# smartwatch_class_2_bottom.net
KiCad netlist of a schematic drawn in EAGLE
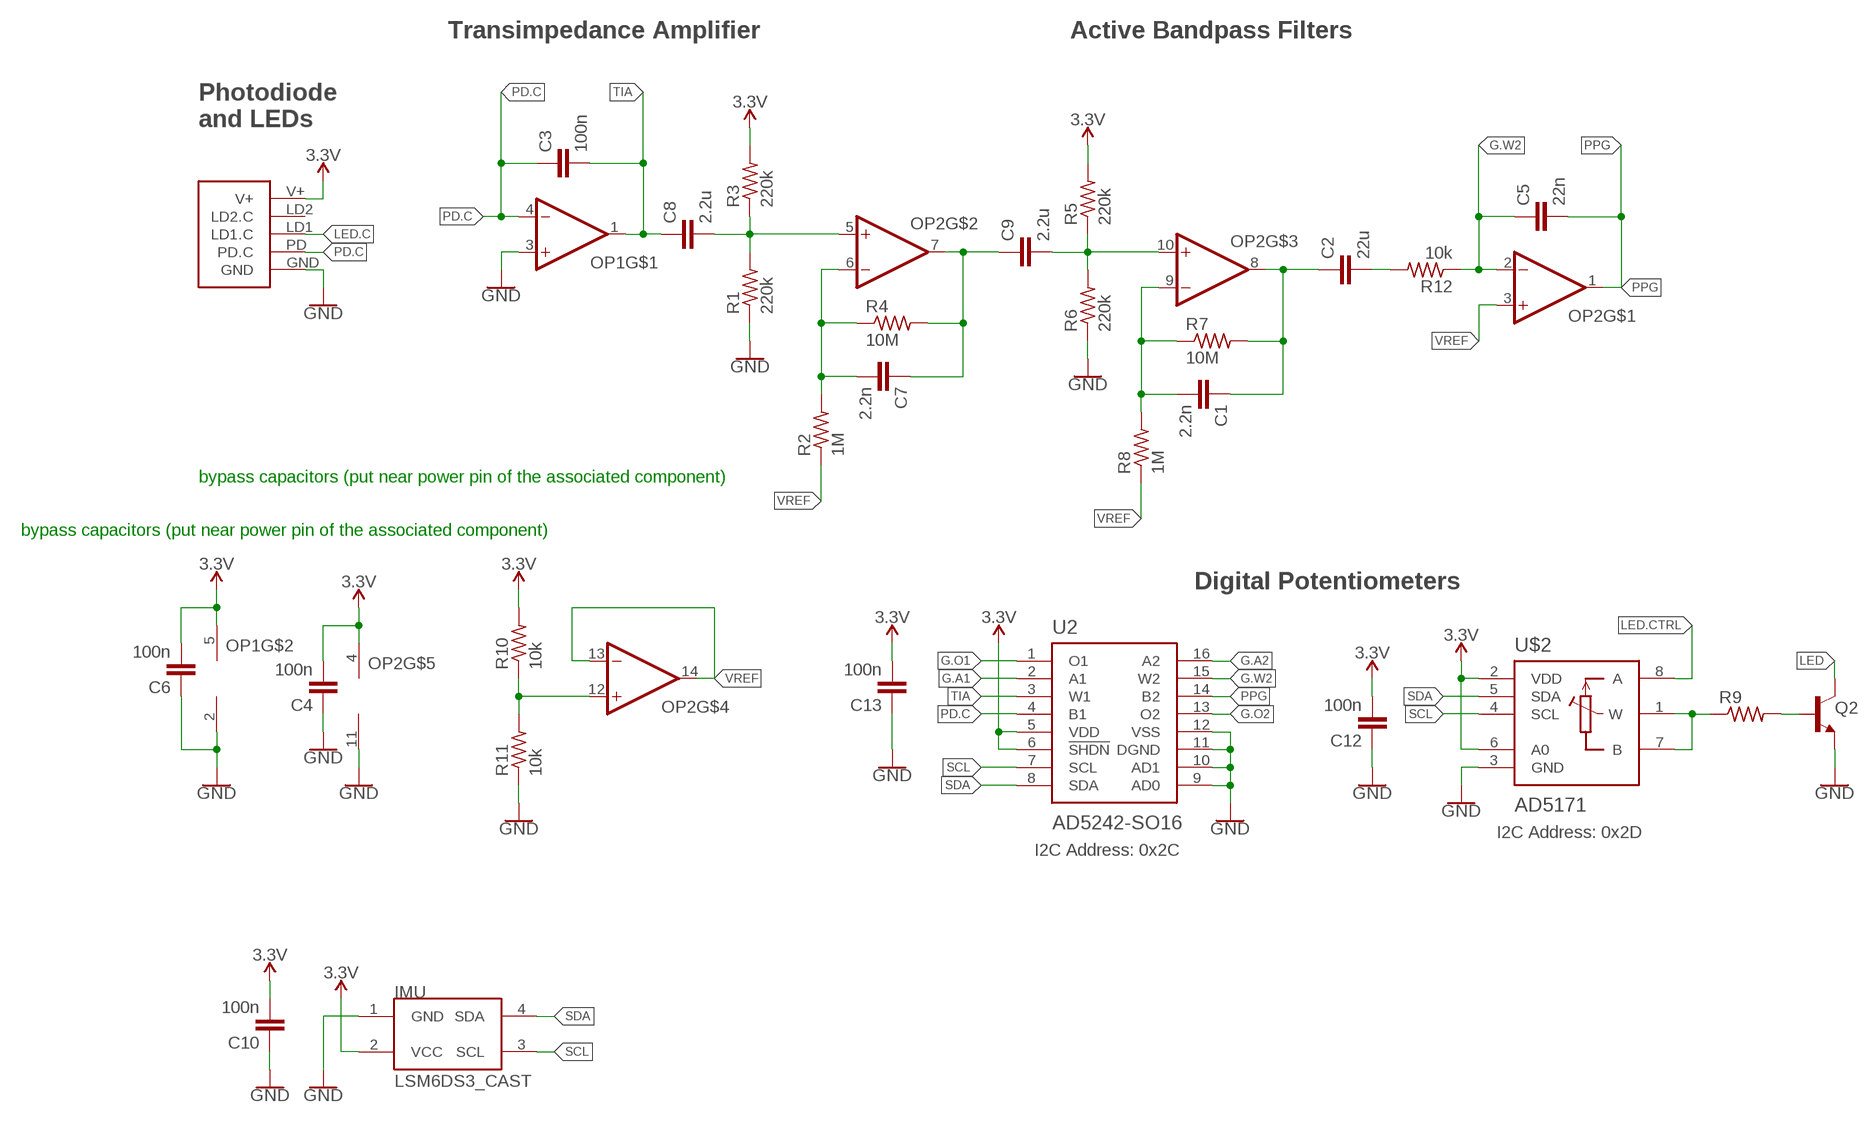
[diagram p0: schematic, sheet 1]

(export (version "E")
  (design (tool "Eeschema 10.0.6"))
  (components
    (comp (ref "C1")
      (value "2.2n")
      (footprint "eagle-import:C0603")
      (libsource (lib "eagle-import") (part "CAPACITOR0603"))
    )
    (comp (ref "C2")
      (value "22u")
      (footprint "eagle-import:C0603")
      (libsource (lib "eagle-import") (part "CAPACITOR0603"))
    )
    (comp (ref "C3")
      (value "100n")
      (footprint "eagle-import:C0603")
      (libsource (lib "eagle-import") (part "CAPACITOR0603"))
    )
    (comp (ref "C4")
      (value "100n")
      (footprint "eagle-import:C0603")
      (libsource (lib "eagle-import") (part "CAPACITOR0603"))
    )
    (comp (ref "C5")
      (value "22n")
      (footprint "eagle-import:C0603")
      (libsource (lib "eagle-import") (part "CAPACITOR0603"))
    )
    (comp (ref "C6")
      (value "100n")
      (footprint "eagle-import:C0603")
      (libsource (lib "eagle-import") (part "CAPACITOR0603"))
    )
    (comp (ref "C7")
      (value "2.2n")
      (footprint "eagle-import:C0603")
      (libsource (lib "eagle-import") (part "CAPACITOR0603"))
    )
    (comp (ref "C8")
      (value "2.2u")
      (footprint "eagle-import:C0603")
      (libsource (lib "eagle-import") (part "CAPACITOR0603"))
    )
    (comp (ref "C9")
      (value "2.2u")
      (footprint "eagle-import:C0603")
      (libsource (lib "eagle-import") (part "CAPACITOR0603"))
    )
    (comp (ref "C10")
      (value "100n")
      (footprint "eagle-import:C0603")
      (libsource (lib "eagle-import") (part "CAPACITOR0603"))
    )
    (comp (ref "C12")
      (value "100n")
      (footprint "eagle-import:C0603")
      (libsource (lib "eagle-import") (part "CAPACITOR0603"))
    )
    (comp (ref "C13")
      (value "100n")
      (footprint "eagle-import:C0603")
      (libsource (lib "eagle-import") (part "CAPACITOR0603"))
    )
    (comp (ref "IMU")
      (value "LSM6DS3_CAST")
      (footprint "eagle-import:LSM6DS3_CAST")
      (libsource (lib "eagle-import") (part "LSM6DS3_CAST"))
    )
    (comp (ref "OP1")
      (value "OP-SINGLEOT")
      (footprint "eagle-import:SOT23-5")
      (libsource (lib "eagle-import") (part "OP-SINGLEOT"))
    )
    (comp (ref "OP2")
      (value "OP-QUAD-SO14")
      (footprint "eagle-import:SO14")
      (libsource (lib "eagle-import") (part "OP-QUAD-SO14"))
    )
    (comp (ref "Q2")
      (value "NPN-GENERIC")
      (footprint "eagle-import:SOT23-3")
      (libsource (lib "eagle-import") (part "NPN-GENERIC"))
    )
    (comp (ref "R1")
      (value "220k")
      (footprint "eagle-import:R0603")
      (libsource (lib "eagle-import") (part "RESISTOR0603"))
    )
    (comp (ref "R2")
      (value "1M")
      (footprint "eagle-import:R0603")
      (libsource (lib "eagle-import") (part "RESISTOR0603"))
    )
    (comp (ref "R3")
      (value "220k")
      (footprint "eagle-import:R0603")
      (libsource (lib "eagle-import") (part "RESISTOR0603"))
    )
    (comp (ref "R4")
      (value "10M")
      (footprint "eagle-import:R0603")
      (libsource (lib "eagle-import") (part "RESISTOR0603"))
    )
    (comp (ref "R5")
      (value "220k")
      (footprint "eagle-import:R0603")
      (libsource (lib "eagle-import") (part "RESISTOR0603"))
    )
    (comp (ref "R6")
      (value "220k")
      (footprint "eagle-import:R0603")
      (libsource (lib "eagle-import") (part "RESISTOR0603"))
    )
    (comp (ref "R7")
      (value "10M")
      (footprint "eagle-import:R0603")
      (libsource (lib "eagle-import") (part "RESISTOR0603"))
    )
    (comp (ref "R8")
      (value "1M")
      (footprint "eagle-import:R0603")
      (libsource (lib "eagle-import") (part "RESISTOR0603"))
    )
    (comp (ref "R9")
      (value "RESISTOR0603")
      (footprint "eagle-import:R0603")
      (libsource (lib "eagle-import") (part "RESISTOR0603"))
    )
    (comp (ref "R10")
      (value "10k")
      (footprint "eagle-import:R0402")
      (libsource (lib "eagle-import") (part "RESISTOR0402"))
    )
    (comp (ref "R11")
      (value "10k")
      (footprint "eagle-import:R0402")
      (libsource (lib "eagle-import") (part "RESISTOR0402"))
    )
    (comp (ref "R12")
      (value "10k")
      (footprint "eagle-import:R0603")
      (libsource (lib "eagle-import") (part "RESISTOR0603"))
    )
    (comp (ref "U$1")
      (value "PPG.MODULE.2")
      (footprint "eagle-import:PPG.MODULE.2")
      (libsource (lib "eagle-import") (part "PPG.MODULE.2"))
    )
    (comp (ref "U$2")
      (value "AD5171")
      (footprint "eagle-import:SOT-23-8")
      (libsource (lib "eagle-import") (part "AD5171"))
    )
    (comp (ref "U2")
      (value "AD5242-SO16")
      (footprint "eagle-import:SO16")
      (libsource (lib "eagle-import") (part "AD5242-SO16"))
    )
  )
  (nets
    (net (code "1") (name "3.3V") (class "Default")
      (node (ref "C10") (pin "2") (pinfunction "2_2") (pintype "passive"))
      (node (ref "C12") (pin "2") (pinfunction "2_2") (pintype "passive"))
      (node (ref "C13") (pin "2") (pinfunction "2_2") (pintype "passive"))
      (node (ref "C4") (pin "2") (pinfunction "2_2") (pintype "passive"))
      (node (ref "C6") (pin "2") (pinfunction "2_2") (pintype "passive"))
      (node (ref "IMU") (pin "2") (pinfunction "VCC_2") (pintype "bidirectional"))
      (node (ref "OP1") (pin "5") (pinfunction "V+_5") (pintype "power_in"))
      (node (ref "OP2") (pin "4") (pinfunction "V+_4") (pintype "power_in"))
      (node (ref "R10") (pin "2") (pinfunction "2_2") (pintype "passive"))
      (node (ref "R3") (pin "2") (pinfunction "2_2") (pintype "passive"))
      (node (ref "R5") (pin "2") (pinfunction "2_2") (pintype "passive"))
      (node (ref "U$1") (pin "V+") (pinfunction "V+_V+") (pintype "bidirectional"))
      (node (ref "U$2") (pin "2") (pinfunction "VDD_2") (pintype "bidirectional"))
      (node (ref "U$2") (pin "6") (pinfunction "A0_6") (pintype "bidirectional"))
      (node (ref "U2") (pin "5") (pinfunction "VDD_5") (pintype "bidirectional"))
      (node (ref "U2") (pin "6") (pinfunction "~{SHDN}_6") (pintype "bidirectional"))
    )
    (net (code "2") (name "G.A1") (class "Default")
      (node (ref "U2") (pin "2") (pinfunction "A1_2") (pintype "bidirectional"))
    )
    (net (code "3") (name "G.A2") (class "Default")
      (node (ref "U2") (pin "16") (pinfunction "A2_16") (pintype "bidirectional"))
    )
    (net (code "4") (name "G.O1") (class "Default")
      (node (ref "U2") (pin "1") (pinfunction "O1_1") (pintype "bidirectional"))
    )
    (net (code "5") (name "G.O2") (class "Default")
      (node (ref "U2") (pin "13") (pinfunction "O2_13") (pintype "bidirectional"))
    )
    (net (code "6") (name "G.W2") (class "Default")
      (node (ref "C5") (pin "1") (pinfunction "1_1") (pintype "passive"))
      (node (ref "OP2") (pin "2") (pinfunction "-IN_2") (pintype "input"))
      (node (ref "R12") (pin "1") (pinfunction "1_1") (pintype "passive"))
      (node (ref "U2") (pin "15") (pinfunction "W2_15") (pintype "bidirectional"))
    )
    (net (code "7") (name "GND") (class "Default")
      (node (ref "C10") (pin "1") (pinfunction "1_1") (pintype "passive"))
      (node (ref "C12") (pin "1") (pinfunction "1_1") (pintype "passive"))
      (node (ref "C13") (pin "1") (pinfunction "1_1") (pintype "passive"))
      (node (ref "C4") (pin "1") (pinfunction "1_1") (pintype "passive"))
      (node (ref "C6") (pin "1") (pinfunction "1_1") (pintype "passive"))
      (node (ref "IMU") (pin "1") (pinfunction "GND_1") (pintype "bidirectional"))
      (node (ref "OP1") (pin "2") (pinfunction "V-_2") (pintype "power_in"))
      (node (ref "OP1") (pin "3") (pinfunction "+IN_3") (pintype "input"))
      (node (ref "OP2") (pin "11") (pinfunction "V-_11") (pintype "power_in"))
      (node (ref "Q2") (pin "2") (pinfunction "E_2") (pintype "passive"))
      (node (ref "R1") (pin "1") (pinfunction "1_1") (pintype "passive"))
      (node (ref "R11") (pin "1") (pinfunction "1_1") (pintype "passive"))
      (node (ref "R6") (pin "1") (pinfunction "1_1") (pintype "passive"))
      (node (ref "U$1") (pin "GND") (pinfunction "GND_GND") (pintype "bidirectional"))
      (node (ref "U$2") (pin "3") (pinfunction "GND_3") (pintype "bidirectional"))
      (node (ref "U2") (pin "10") (pinfunction "AD1_10") (pintype "bidirectional"))
      (node (ref "U2") (pin "11") (pinfunction "DGND_11") (pintype "bidirectional"))
      (node (ref "U2") (pin "12") (pinfunction "VSS_12") (pintype "bidirectional"))
      (node (ref "U2") (pin "9") (pinfunction "AD0_9") (pintype "bidirectional"))
    )
    (net (code "8") (name "LED") (class "Default")
      (node (ref "Q2") (pin "3") (pinfunction "C_3") (pintype "passive"))
    )
    (net (code "9") (name "LED.C") (class "Default")
      (node (ref "U$1") (pin "LD1") (pinfunction "LD1.C_LD1") (pintype "bidirectional"))
    )
    (net (code "10") (name "LED.CTRL") (class "Default")
      (node (ref "U$2") (pin "8") (pinfunction "A_8") (pintype "bidirectional"))
    )
    (net (code "11") (name "Net-(C2-Pad2)") (class "Default")
      (node (ref "C2") (pin "2") (pinfunction "2_2") (pintype "passive"))
      (node (ref "R12") (pin "2") (pinfunction "2_2") (pintype "passive"))
    )
    (net (code "12") (name "Net-(OP2B-+IN)") (class "Default")
      (node (ref "C8") (pin "2") (pinfunction "2_2") (pintype "passive"))
      (node (ref "OP2") (pin "5") (pinfunction "+IN_5") (pintype "input"))
      (node (ref "R1") (pin "2") (pinfunction "2_2") (pintype "passive"))
      (node (ref "R3") (pin "1") (pinfunction "1_1") (pintype "passive"))
    )
    (net (code "13") (name "Net-(OP2B--IN)") (class "Default")
      (node (ref "C7") (pin "2") (pinfunction "2_2") (pintype "passive"))
      (node (ref "OP2") (pin "6") (pinfunction "-IN_6") (pintype "input"))
      (node (ref "R2") (pin "2") (pinfunction "2_2") (pintype "passive"))
      (node (ref "R4") (pin "1") (pinfunction "1_1") (pintype "passive"))
    )
    (net (code "14") (name "Net-(OP2B-OUT)") (class "Default")
      (node (ref "C7") (pin "1") (pinfunction "1_1") (pintype "passive"))
      (node (ref "C9") (pin "1") (pinfunction "1_1") (pintype "passive"))
      (node (ref "OP2") (pin "7") (pinfunction "OUT_7") (pintype "output"))
      (node (ref "R4") (pin "2") (pinfunction "2_2") (pintype "passive"))
    )
    (net (code "15") (name "Net-(OP2C-+IN)") (class "Default")
      (node (ref "C9") (pin "2") (pinfunction "2_2") (pintype "passive"))
      (node (ref "OP2") (pin "10") (pinfunction "+IN_10") (pintype "input"))
      (node (ref "R5") (pin "1") (pinfunction "1_1") (pintype "passive"))
      (node (ref "R6") (pin "2") (pinfunction "2_2") (pintype "passive"))
    )
    (net (code "16") (name "Net-(OP2C--IN)") (class "Default")
      (node (ref "C1") (pin "2") (pinfunction "2_2") (pintype "passive"))
      (node (ref "OP2") (pin "9") (pinfunction "-IN_9") (pintype "input"))
      (node (ref "R7") (pin "1") (pinfunction "1_1") (pintype "passive"))
      (node (ref "R8") (pin "2") (pinfunction "2_2") (pintype "passive"))
    )
    (net (code "17") (name "Net-(OP2C-OUT)") (class "Default")
      (node (ref "C1") (pin "1") (pinfunction "1_1") (pintype "passive"))
      (node (ref "C2") (pin "1") (pinfunction "1_1") (pintype "passive"))
      (node (ref "OP2") (pin "8") (pinfunction "OUT_8") (pintype "output"))
      (node (ref "R7") (pin "2") (pinfunction "2_2") (pintype "passive"))
    )
    (net (code "18") (name "Net-(OP2D-+IN)") (class "Default")
      (node (ref "OP2") (pin "12") (pinfunction "+IN_12") (pintype "input"))
      (node (ref "R10") (pin "1") (pinfunction "1_1") (pintype "passive"))
      (node (ref "R11") (pin "2") (pinfunction "2_2") (pintype "passive"))
    )
    (net (code "19") (name "Net-(Q2-B)") (class "Default")
      (node (ref "Q2") (pin "1") (pinfunction "B_1") (pintype "passive"))
      (node (ref "R9") (pin "2") (pinfunction "2_2") (pintype "passive"))
    )
    (net (code "20") (name "Net-(U$2-B)") (class "Default")
      (node (ref "R9") (pin "1") (pinfunction "1_1") (pintype "passive"))
      (node (ref "U$2") (pin "1") (pinfunction "W_1") (pintype "bidirectional"))
      (node (ref "U$2") (pin "7") (pinfunction "B_7") (pintype "bidirectional"))
    )
    (net (code "21") (name "PD.C") (class "Default")
      (node (ref "C3") (pin "1") (pinfunction "1_1") (pintype "passive"))
      (node (ref "OP1") (pin "4") (pinfunction "-IN_4") (pintype "input"))
      (node (ref "U$1") (pin "PD") (pinfunction "PD.C_PD") (pintype "bidirectional"))
      (node (ref "U2") (pin "4") (pinfunction "B1_4") (pintype "bidirectional"))
    )
    (net (code "22") (name "PPG") (class "Default")
      (node (ref "C5") (pin "2") (pinfunction "2_2") (pintype "passive"))
      (node (ref "OP2") (pin "1") (pinfunction "OUT_1") (pintype "output"))
      (node (ref "U2") (pin "14") (pinfunction "B2_14") (pintype "bidirectional"))
    )
    (net (code "23") (name "SCL") (class "Default")
      (node (ref "IMU") (pin "3") (pinfunction "SCL_3") (pintype "bidirectional"))
      (node (ref "U$2") (pin "4") (pinfunction "SCL_4") (pintype "bidirectional"))
      (node (ref "U2") (pin "7") (pinfunction "SCL_7") (pintype "bidirectional"))
    )
    (net (code "24") (name "SDA") (class "Default")
      (node (ref "IMU") (pin "4") (pinfunction "SDA_4") (pintype "bidirectional"))
      (node (ref "U$2") (pin "5") (pinfunction "SDA_5") (pintype "bidirectional"))
      (node (ref "U2") (pin "8") (pinfunction "SDA_8") (pintype "bidirectional"))
    )
    (net (code "25") (name "TIA") (class "Default")
      (node (ref "C3") (pin "2") (pinfunction "2_2") (pintype "passive"))
      (node (ref "C8") (pin "1") (pinfunction "1_1") (pintype "passive"))
      (node (ref "OP1") (pin "1") (pinfunction "OUT_1") (pintype "output"))
      (node (ref "U2") (pin "3") (pinfunction "W1_3") (pintype "bidirectional"))
    )
    (net (code "26") (name "VREF") (class "Default")
      (node (ref "OP2") (pin "13") (pinfunction "-IN_13") (pintype "input"))
      (node (ref "OP2") (pin "14") (pinfunction "OUT_14") (pintype "output"))
      (node (ref "OP2") (pin "3") (pinfunction "+IN_3") (pintype "input"))
      (node (ref "R2") (pin "1") (pinfunction "1_1") (pintype "passive"))
      (node (ref "R8") (pin "1") (pinfunction "1_1") (pintype "passive"))
    )
    (net (code "27") (name "unconnected-(U$1-LD2.C-PadLD2)") (class "Default")
      (node (ref "U$1") (pin "LD2") (pinfunction "LD2.C_LD2") (pintype "bidirectional"))
    )
  )
)
